# SSFocuser-B-TMC2208.net
KiCad netlist of a schematic drawn in Altium Designer
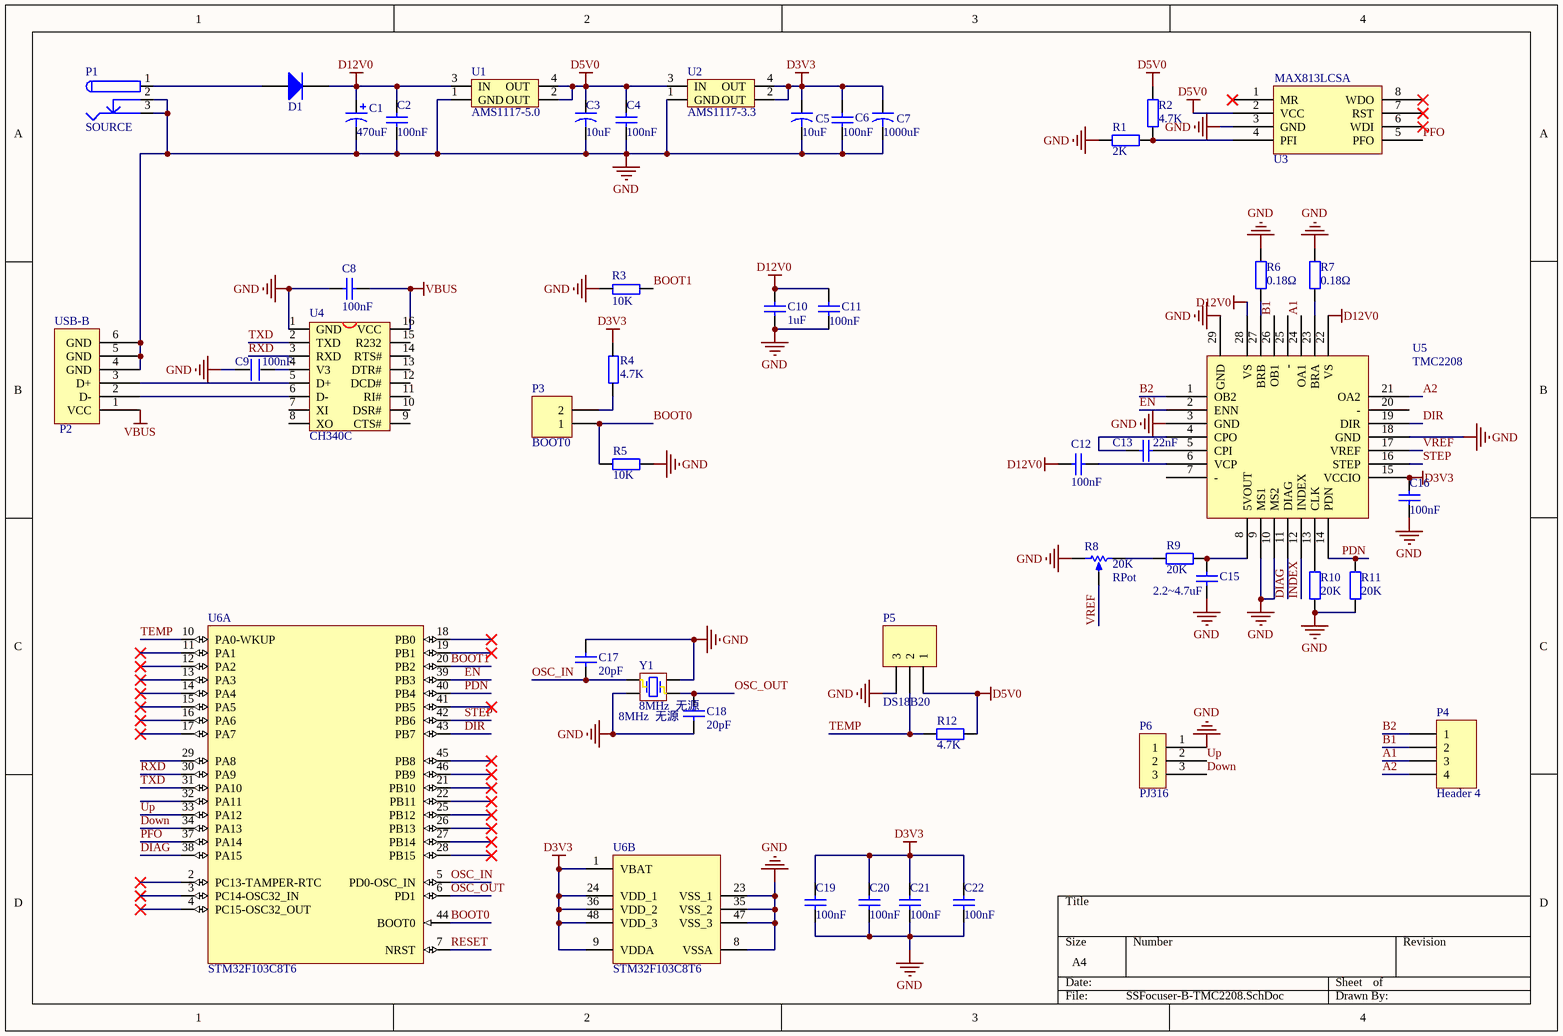
[diagram p0: SSFocuser-B-TMC2208.SchDoc]

(export (version "E")
  (design (tool "Eeschema 10.0.6"))
  (components
    (comp (ref "C1")
      (value "470uF")
      (footprint "16V/470U(CD10X10D5)")
      (description "470UF      16V      CD10X10D5")
      (libsource (lib "平台原理图symbol图库V1.0") (part "C470UF016S"))
    )
    (comp (ref "C2")
      (value "100nF")
      (footprint "0603C")
      (description "Capacitor")
      (fields (field (name "PUBLISHER") "Altium Limited"))
      (libsource (lib "Crazy_PCB") (part "Cap"))
    )
    (comp (ref "C3")
      (value "10uF")
      (footprint "3216")
      (fields (field (name "VAULE") "10uF"))
      (libsource (lib "Crazy_PCB") (part "CAP2"))
    )
    (comp (ref "C4")
      (value "100nF")
      (footprint "0603C")
      (description "Capacitor")
      (fields (field (name "PUBLISHER") "Altium Limited"))
      (libsource (lib "Crazy_PCB") (part "Cap"))
    )
    (comp (ref "C5")
      (value "10uF")
      (footprint "3216")
      (fields (field (name "VAULE") "10uF"))
      (libsource (lib "Crazy_PCB") (part "CAP2"))
    )
    (comp (ref "C6")
      (value "100nF")
      (footprint "0603C")
      (description "Capacitor")
      (fields (field (name "PUBLISHER") "Altium Limited"))
      (libsource (lib "Crazy_PCB") (part "Cap"))
    )
    (comp (ref "C7")
      (value "1000uF")
      (footprint "16V/470U(CD10X10D5)")
      (fields (field (name "VAULE") "1000uF"))
      (libsource (lib "Crazy_PCB") (part "CAP2"))
    )
    (comp (ref "C8")
      (value "100nF")
      (footprint "0603C")
      (description "Capacitor")
      (fields (field (name "PUBLISHER") "Altium Limited"))
      (libsource (lib "Crazy_PCB") (part "Cap"))
    )
    (comp (ref "C9")
      (value "100nF")
      (footprint "0603C")
      (libsource (lib "WarShip V3 STM32103封装库") (part "C"))
    )
    (comp (ref "C10")
      (value "1uF")
      (footprint "1206C")
      (description "Capacitor")
      (fields (field (name "PUBLISHER") "Altium Limited"))
      (libsource (lib "Crazy_PCB") (part "Cap"))
    )
    (comp (ref "C11")
      (value "100nF")
      (footprint "0603C")
      (description "Capacitor")
      (fields (field (name "PUBLISHER") "Altium Limited"))
      (libsource (lib "Crazy_PCB") (part "Cap"))
    )
    (comp (ref "C12")
      (value "100nF")
      (footprint "0603C")
      (description "Capacitor")
      (fields (field (name "PUBLISHER") "Altium Limited"))
      (libsource (lib "Crazy_PCB") (part "Cap"))
    )
    (comp (ref "C13")
      (value "22nF")
      (footprint "0603C")
      (description "Capacitor")
      (fields (field (name "PUBLISHER") "Altium Limited"))
      (libsource (lib "Crazy_PCB") (part "Cap"))
    )
    (comp (ref "C15")
      (value "2.2~4.7uF")
      (footprint "0603C")
      (description "Capacitor")
      (fields (field (name "PUBLISHER") "Altium Limited"))
      (libsource (lib "Crazy_PCB") (part "Cap"))
    )
    (comp (ref "C16")
      (value "100nF")
      (footprint "0603C")
      (description "Capacitor")
      (fields (field (name "PUBLISHER") "Altium Limited"))
      (libsource (lib "Crazy_PCB") (part "Cap"))
    )
    (comp (ref "C17")
      (value "20pF")
      (footprint "0603C")
      (description "Capacitor")
      (fields (field (name "PUBLISHER") "Altium Limited"))
      (libsource (lib "JL_SCH") (part "Cap"))
    )
    (comp (ref "C18")
      (value "20pF")
      (footprint "0603C")
      (description "Capacitor")
      (fields (field (name "PUBLISHER") "Altium Limited"))
      (libsource (lib "JL_SCH") (part "Cap"))
    )
    (comp (ref "C19")
      (value "100nF")
      (footprint "0603C")
      (description "Capacitor")
      (fields (field (name "PUBLISHER") "Altium Limited"))
      (libsource (lib "Crazy_PCB") (part "Cap"))
    )
    (comp (ref "C20")
      (value "100nF")
      (footprint "0603C")
      (description "Capacitor")
      (fields (field (name "PUBLISHER") "Altium Limited"))
      (libsource (lib "Crazy_PCB") (part "Cap"))
    )
    (comp (ref "C21")
      (value "100nF")
      (footprint "0603C")
      (description "Capacitor")
      (fields (field (name "PUBLISHER") "Altium Limited"))
      (libsource (lib "Crazy_PCB") (part "Cap"))
    )
    (comp (ref "C22")
      (value "100nF")
      (footprint "0603C")
      (description "Capacitor")
      (fields (field (name "PUBLISHER") "Altium Limited"))
      (libsource (lib "Crazy_PCB") (part "Cap"))
    )
    (comp (ref "D1")
      (value "M7")
      (footprint "DO-214AC")
      (description "High Conductance Fast Diode")
      (fields (field (name "PUBLISHER") "Altium Limited"))
      (libsource (lib "Crazy_PCB") (part "Diode"))
    )
    (comp (ref "P1")
      (value "SOURCE")
      (footprint "DC_5.5MM")
      (fields (field (name "PUBLISHER") "Altium Limited"))
      (libsource (lib "Crazy_PCB") (part "SOURCE"))
    )
    (comp (ref "P2") (value "USB-B") (footprint "USB-B") (libsource (lib "DX") (part "USB-B")))
    (comp (ref "P3")
      (value "BOOT0")
      (footprint "HDR1X2")
      (description "Header, 2-Pin")
      (fields (field (name "PUBLISHER") "Altium Limited"))
      (libsource (lib "Miscellaneous Connectors") (part "MHDR1X2"))
    )
    (comp (ref "P4")
      (value "Header 4")
      (footprint "XH_4_V")
      (description "Header, 4-Pin")
      (fields (field (name "PUBLISHER") "Altium Limited"))
      (libsource (lib "Miscellaneous Connectors") (part "Header 4"))
    )
    (comp (ref "P5")
      (value "DS18B20")
      (footprint "TO-92B")
      (description "Header, 3-Pin")
      (fields (field (name "PUBLISHER") "Altium Limited"))
      (libsource (lib "Miscellaneous Connectors") (part "Header 3"))
    )
    (comp (ref "P6") (value "PJ316") (footprint "PJ316") (libsource (lib "SS") (part "PJ316")))
    (comp (ref "R1")
      (value "2K")
      (footprint "0603R")
      (description "Resistor")
      (fields (field (name "PUBLISHER") "Altium Limited"))
      (libsource (lib "") (part "RES_3"))
    )
    (comp (ref "R2")
      (value "4.7K")
      (footprint "0603R")
      (description "Resistor")
      (fields (field (name "PUBLISHER") "Altium Limited"))
      (libsource (lib "") (part "RES_1"))
    )
    (comp (ref "R3") (value "10K") (footprint "0603R") (libsource (lib "WarShip V3 STM32103封装库") (part "R")))
    (comp (ref "R4") (value "4.7K") (footprint "0603R") (libsource (lib "WarShip V3 STM32103封装库") (part "R")))
    (comp (ref "R5")
      (value "10K")
      (footprint "0603R")
      (description "Resistor")
      (fields (field (name "PUBLISHER") "Altium Limited"))
      (libsource (lib "") (part "RES_2"))
    )
    (comp (ref "R6")
      (value "0.18Ω")
      (footprint "1206R")
      (description "Resistor")
      (fields (field (name "PUBLISHER") "Altium Limited"))
      (libsource (lib "Crazy_PCB") (part "RES"))
    )
    (comp (ref "R7")
      (value "0.18Ω")
      (footprint "1206R")
      (description "Resistor")
      (fields (field (name "PUBLISHER") "Altium Limited"))
      (libsource (lib "Crazy_PCB") (part "RES"))
    )
    (comp (ref "R8")
      (value "RPot")
      (footprint "VR_SMD")
      (description "Potentiometer")
      (fields (field (name "ALTIUM_VALUE") "20K") (field (name "PUBLISHER") "Altium Limited"))
      (libsource (lib "Miscellaneous Devices") (part "RPot"))
    )
    (comp (ref "R9")
      (value "20K")
      (footprint "0603R")
      (description "Resistor")
      (fields (field (name "PUBLISHER") "Altium Limited"))
      (libsource (lib "") (part "RES_3"))
    )
    (comp (ref "R10")
      (value "20K")
      (footprint "0603R")
      (description "Resistor")
      (fields (field (name "PUBLISHER") "Altium Limited"))
      (libsource (lib "") (part "RES_1"))
    )
    (comp (ref "R11")
      (value "20K")
      (footprint "0603R")
      (description "Resistor")
      (fields (field (name "PUBLISHER") "Altium Limited"))
      (libsource (lib "") (part "RES_1"))
    )
    (comp (ref "R12")
      (value "4.7K")
      (footprint "0603R")
      (description "Resistor")
      (fields (field (name "PUBLISHER") "Altium Limited"))
      (libsource (lib "") (part "RES_2"))
    )
    (comp (ref "U1")
      (value "AMS1117-5.0")
      (footprint "SOT223")
      (libsource (lib "MiniSTM32 V3.0封装库") (part "AMS1117"))
    )
    (comp (ref "U2")
      (value "AMS1117-3.3")
      (footprint "SOT223")
      (libsource (lib "MiniSTM32 V3.0封装库") (part "AMS1117"))
    )
    (comp (ref "U3") (value "MAX813LCSA") (footprint "SOP-8") (libsource (lib "DX") (part "MAX813L")))
    (comp (ref "U4")
      (value "CH340C")
      (footprint "SO-16")
      (description "USB2UART")
      (libsource (lib "WarShip V3 STM32103封装库") (part "CH340G"))
    )
    (comp (ref "U5") (value "TMC2208") (footprint "QFN28") (libsource (lib "SS") (part "TMC2208")))
    (comp (ref "U6")
      (value "STM32F103C8T6")
      (footprint "LQFP48_N")
      (libsource (lib "STMicroelectronics STM32 F1") (part "STM32F103C8T6"))
    )
    (comp (ref "Y1")
      (value "8MHz  无源")
      (footprint "X3225")
      (description "Crystal Oscillator")
      (fields (field (name "ALTIUM_VALUE") "8MHz  无源") (field (name "PUBLISHER") "Altium Limited"))
      (libsource (lib "JL_SCH") (part "XTAL_1"))
    )
  )
  (nets
    (net (code "1") (name "/A1") (class "Default")
      (node (ref "P4") (pin "3") (pinfunction "3_3") (pintype "passive"))
      (node (ref "U5") (pin "24") (pinfunction "OA1_24") (pintype "passive"))
    )
    (net (code "2") (name "/A2") (class "Default")
      (node (ref "P4") (pin "4") (pinfunction "4_4") (pintype "passive"))
      (node (ref "U5") (pin "21") (pinfunction "OA2_21") (pintype "passive"))
    )
    (net (code "3") (name "/B1") (class "Default")
      (node (ref "P4") (pin "2") (pinfunction "2_2") (pintype "passive"))
      (node (ref "U5") (pin "26") (pinfunction "OB1_26") (pintype "passive"))
    )
    (net (code "4") (name "/B2") (class "Default")
      (node (ref "P4") (pin "1") (pinfunction "1_1") (pintype "passive"))
      (node (ref "U5") (pin "1") (pinfunction "OB2_1") (pintype "passive"))
    )
    (net (code "5") (name "/BOOT0") (class "Default")
      (node (ref "P3") (pin "1") (pinfunction "1_1") (pintype "passive"))
      (node (ref "R5") (pin "1") (pinfunction "1_1") (pintype "passive"))
      (node (ref "U6") (pin "44") (pinfunction "BOOT0_44") (pintype "input"))
    )
    (net (code "6") (name "/BOOT1") (class "Default")
      (node (ref "R3") (pin "2") (pintype "passive"))
      (node (ref "U6") (pin "20") (pinfunction "PB2_20") (pintype "bidirectional"))
    )
    (net (code "7") (name "/DIAG") (class "Default")
      (node (ref "U5") (pin "11") (pinfunction "DIAG_11") (pintype "passive"))
      (node (ref "U6") (pin "38") (pinfunction "PA15_38") (pintype "bidirectional"))
    )
    (net (code "8") (name "/DIR") (class "Default")
      (node (ref "U5") (pin "19") (pinfunction "DIR_19") (pintype "passive"))
      (node (ref "U6") (pin "43") (pinfunction "PB7_43") (pintype "bidirectional"))
    )
    (net (code "9") (name "/Down") (class "Default")
      (node (ref "P6") (pin "3") (pinfunction "3_3") (pintype "passive"))
      (node (ref "U6") (pin "34") (pinfunction "PA13_34") (pintype "bidirectional"))
    )
    (net (code "10") (name "/EN") (class "Default")
      (node (ref "U5") (pin "2") (pinfunction "ENN_2") (pintype "passive"))
      (node (ref "U6") (pin "39") (pinfunction "PB3_39") (pintype "bidirectional"))
    )
    (net (code "11") (name "/INDEX") (class "Default")
      (node (ref "U5") (pin "12") (pinfunction "INDEX_12") (pintype "passive"))
    )
    (net (code "12") (name "/OSC_IN") (class "Default")
      (node (ref "C17") (pin "1") (pinfunction "1_1") (pintype "passive"))
      (node (ref "U6") (pin "5") (pinfunction "PD0-OSC_IN_5") (pintype "bidirectional"))
      (node (ref "Y1") (pin "1") (pinfunction "OSC1_1") (pintype "passive"))
    )
    (net (code "13") (name "/OSC_OUT") (class "Default")
      (node (ref "C18") (pin "1") (pinfunction "1_1") (pintype "passive"))
      (node (ref "U6") (pin "6") (pinfunction "PD1_6") (pintype "bidirectional"))
      (node (ref "Y1") (pin "3") (pinfunction "OSC2_3") (pintype "passive"))
    )
    (net (code "14") (name "/PDN") (class "Default")
      (node (ref "R11") (pin "2") (pinfunction "2_2") (pintype "passive"))
      (node (ref "U5") (pin "14") (pinfunction "PDN_14") (pintype "passive"))
      (node (ref "U6") (pin "40") (pinfunction "PB4_40") (pintype "bidirectional"))
    )
    (net (code "15") (name "/PFO") (class "Default")
      (node (ref "U3") (pin "5") (pinfunction "PFO_5") (pintype "passive"))
      (node (ref "U6") (pin "37") (pinfunction "PA14_37") (pintype "bidirectional"))
    )
    (net (code "16") (name "/RESET") (class "Default")
      (node (ref "U6") (pin "7") (pinfunction "NRST_7") (pintype "bidirectional"))
    )
    (net (code "17") (name "/RXD") (class "Default")
      (node (ref "U4") (pin "3") (pinfunction "RXD_3") (pintype "passive"))
      (node (ref "U6") (pin "30") (pinfunction "PA9_30") (pintype "bidirectional"))
    )
    (net (code "18") (name "/STEP") (class "Default")
      (node (ref "U5") (pin "16") (pinfunction "STEP_16") (pintype "passive"))
      (node (ref "U6") (pin "42") (pinfunction "PB6_42") (pintype "bidirectional"))
    )
    (net (code "19") (name "/TEMP") (class "Default")
      (node (ref "P5") (pin "2") (pinfunction "2_2") (pintype "passive"))
      (node (ref "R12") (pin "1") (pinfunction "1_1") (pintype "passive"))
      (node (ref "U6") (pin "10") (pinfunction "PA0-WKUP_10") (pintype "bidirectional"))
    )
    (net (code "20") (name "/TXD") (class "Default")
      (node (ref "U4") (pin "2") (pinfunction "TXD_2") (pintype "passive"))
      (node (ref "U6") (pin "31") (pinfunction "PA10_31") (pintype "bidirectional"))
    )
    (net (code "21") (name "/Up") (class "Default")
      (node (ref "P6") (pin "2") (pinfunction "2_2") (pintype "passive"))
      (node (ref "U6") (pin "33") (pinfunction "PA12_33") (pintype "bidirectional"))
    )
    (net (code "22") (name "/VREF") (class "Default")
      (node (ref "R8") (pin "3") (pinfunction "TAP_3") (pintype "passive"))
      (node (ref "U5") (pin "17") (pinfunction "VREF_17") (pintype "passive"))
    )
    (net (code "23") (name "D3V3") (class "Default")
      (node (ref "C16") (pin "2") (pinfunction "2_2") (pintype "passive"))
      (node (ref "C19") (pin "2") (pinfunction "2_2") (pintype "passive"))
      (node (ref "C20") (pin "2") (pinfunction "2_2") (pintype "passive"))
      (node (ref "C21") (pin "2") (pinfunction "2_2") (pintype "passive"))
      (node (ref "C22") (pin "2") (pinfunction "2_2") (pintype "passive"))
      (node (ref "C5") (pin "1") (pinfunction "1_1") (pintype "passive"))
      (node (ref "C6") (pin "2") (pinfunction "2_2") (pintype "passive"))
      (node (ref "C7") (pin "1") (pinfunction "1_1") (pintype "passive"))
      (node (ref "R4") (pin "2") (pintype "passive"))
      (node (ref "U2") (pin "2") (pinfunction "OUT_2") (pintype "passive"))
      (node (ref "U2") (pin "4") (pinfunction "OUT_4") (pintype "passive"))
      (node (ref "U5") (pin "15") (pinfunction "VCCIO_15") (pintype "passive"))
      (node (ref "U6") (pin "1") (pinfunction "VBAT_1") (pintype "power_in"))
      (node (ref "U6") (pin "24") (pinfunction "VDD_1_24") (pintype "power_in"))
      (node (ref "U6") (pin "36") (pinfunction "VDD_2_36") (pintype "power_in"))
      (node (ref "U6") (pin "48") (pinfunction "VDD_3_48") (pintype "power_in"))
      (node (ref "U6") (pin "9") (pinfunction "VDDA_9") (pintype "power_in"))
    )
    (net (code "24") (name "D5V0") (class "Default")
      (node (ref "C3") (pin "1") (pinfunction "1_1") (pintype "passive"))
      (node (ref "C4") (pin "2") (pinfunction "2_2") (pintype "passive"))
      (node (ref "P5") (pin "1") (pinfunction "1_1") (pintype "passive"))
      (node (ref "R12") (pin "2") (pinfunction "2_2") (pintype "passive"))
      (node (ref "R2") (pin "2") (pinfunction "2_2") (pintype "passive"))
      (node (ref "U1") (pin "2") (pinfunction "OUT_2") (pintype "passive"))
      (node (ref "U1") (pin "4") (pinfunction "OUT_4") (pintype "passive"))
      (node (ref "U2") (pin "3") (pinfunction "IN_3") (pintype "passive"))
      (node (ref "U3") (pin "2") (pinfunction "VCC_2") (pintype "passive"))
    )
    (net (code "25") (name "D12V0") (class "Default")
      (node (ref "C1") (pin "1") (pinfunction "1_1") (pintype "passive"))
      (node (ref "C10") (pin "1") (pinfunction "1_1") (pintype "passive"))
      (node (ref "C11") (pin "2") (pinfunction "2_2") (pintype "passive"))
      (node (ref "C12") (pin "2") (pinfunction "2_2") (pintype "passive"))
      (node (ref "C2") (pin "2") (pinfunction "2_2") (pintype "passive"))
      (node (ref "D1") (pin "2") (pinfunction "K_2") (pintype "passive"))
      (node (ref "U1") (pin "3") (pinfunction "IN_3") (pintype "passive"))
      (node (ref "U5") (pin "22") (pinfunction "VS_22") (pintype "passive"))
      (node (ref "U5") (pin "28") (pinfunction "VS_28") (pintype "passive"))
    )
    (net (code "26") (name "GND") (class "Default")
      (node (ref "C1") (pin "2") (pinfunction "2_2") (pintype "passive"))
      (node (ref "C10") (pin "2") (pinfunction "2_2") (pintype "passive"))
      (node (ref "C11") (pin "1") (pinfunction "1_1") (pintype "passive"))
      (node (ref "C15") (pin "1") (pinfunction "1_1") (pintype "passive"))
      (node (ref "C16") (pin "1") (pinfunction "1_1") (pintype "passive"))
      (node (ref "C17") (pin "2") (pinfunction "2_2") (pintype "passive"))
      (node (ref "C18") (pin "2") (pinfunction "2_2") (pintype "passive"))
      (node (ref "C19") (pin "1") (pinfunction "1_1") (pintype "passive"))
      (node (ref "C2") (pin "1") (pinfunction "1_1") (pintype "passive"))
      (node (ref "C20") (pin "1") (pinfunction "1_1") (pintype "passive"))
      (node (ref "C21") (pin "1") (pinfunction "1_1") (pintype "passive"))
      (node (ref "C22") (pin "1") (pinfunction "1_1") (pintype "passive"))
      (node (ref "C3") (pin "2") (pinfunction "2_2") (pintype "passive"))
      (node (ref "C4") (pin "1") (pinfunction "1_1") (pintype "passive"))
      (node (ref "C5") (pin "2") (pinfunction "2_2") (pintype "passive"))
      (node (ref "C6") (pin "1") (pinfunction "1_1") (pintype "passive"))
      (node (ref "C7") (pin "2") (pinfunction "2_2") (pintype "passive"))
      (node (ref "C8") (pin "1") (pinfunction "1_1") (pintype "passive"))
      (node (ref "C9") (pin "1") (pintype "passive"))
      (node (ref "P1") (pin "2") (pinfunction "2_2") (pintype "power_in"))
      (node (ref "P1") (pin "3") (pinfunction "3_3") (pintype "power_in"))
      (node (ref "P2") (pin "4") (pinfunction "GND_4") (pintype "passive"))
      (node (ref "P2") (pin "5") (pinfunction "GND_5") (pintype "passive"))
      (node (ref "P2") (pin "6") (pinfunction "GND_6") (pintype "passive"))
      (node (ref "P5") (pin "3") (pinfunction "3_3") (pintype "passive"))
      (node (ref "P6") (pin "1") (pinfunction "1_1") (pintype "passive"))
      (node (ref "R1") (pin "2") (pinfunction "2_2") (pintype "passive"))
      (node (ref "R10") (pin "1") (pinfunction "1_1") (pintype "passive"))
      (node (ref "R11") (pin "1") (pinfunction "1_1") (pintype "passive"))
      (node (ref "R3") (pin "1") (pintype "passive"))
      (node (ref "R5") (pin "2") (pinfunction "2_2") (pintype "passive"))
      (node (ref "R6") (pin "1") (pinfunction "1_1") (pintype "passive"))
      (node (ref "R7") (pin "1") (pinfunction "1_1") (pintype "passive"))
      (node (ref "R8") (pin "1") (pinfunction "TOP_1") (pintype "passive"))
      (node (ref "U1") (pin "1") (pinfunction "GND_1") (pintype "passive"))
      (node (ref "U2") (pin "1") (pinfunction "GND_1") (pintype "passive"))
      (node (ref "U3") (pin "3") (pinfunction "GND_3") (pintype "passive"))
      (node (ref "U4") (pin "1") (pinfunction "GND_1") (pintype "passive"))
      (node (ref "U5") (pin "10") (pinfunction "MS2_10") (pintype "passive"))
      (node (ref "U5") (pin "18") (pinfunction "GND_18") (pintype "passive"))
      (node (ref "U5") (pin "29") (pinfunction "GND_29") (pintype "passive"))
      (node (ref "U5") (pin "3") (pinfunction "GND_3") (pintype "passive"))
      (node (ref "U5") (pin "9") (pinfunction "MS1_9") (pintype "passive"))
      (node (ref "U6") (pin "23") (pinfunction "VSS_1_23") (pintype "power_in"))
      (node (ref "U6") (pin "35") (pinfunction "VSS_2_35") (pintype "power_in"))
      (node (ref "U6") (pin "47") (pinfunction "VSS_3_47") (pintype "power_in"))
      (node (ref "U6") (pin "8") (pinfunction "VSSA_8") (pintype "power_in"))
      (node (ref "Y1") (pin "2") (pinfunction "NA_2") (pintype "passive"))
      (node (ref "Y1") (pin "4") (pinfunction "NA_4") (pintype "passive"))
    )
    (net (code "27") (name "Net-(D1-A)") (class "Default")
      (node (ref "D1") (pin "1") (pinfunction "A_1") (pintype "passive"))
      (node (ref "P1") (pin "1") (pinfunction "1_1") (pintype "power_in"))
    )
    (net (code "28") (name "Net-(P2-D+)") (class "Default")
      (node (ref "P2") (pin "3") (pinfunction "D+_3") (pintype "passive"))
      (node (ref "U4") (pin "5") (pinfunction "D+_5") (pintype "passive"))
    )
    (net (code "29") (name "Net-(P2-D-)") (class "Default")
      (node (ref "P2") (pin "2") (pinfunction "D-_2") (pintype "passive"))
      (node (ref "U4") (pin "6") (pinfunction "D-_6") (pintype "passive"))
    )
    (net (code "30") (name "Net-(P3-Pad2)") (class "Default")
      (node (ref "P3") (pin "2") (pinfunction "2_2") (pintype "passive"))
      (node (ref "R4") (pin "1") (pintype "passive"))
    )
    (net (code "31") (name "Net-(R8-BOT)") (class "Default")
      (node (ref "R8") (pin "2") (pinfunction "BOT_2") (pintype "passive"))
      (node (ref "R9") (pin "2") (pinfunction "2_2") (pintype "passive"))
    )
    (net (code "32") (name "Net-(U3-PFI)") (class "Default")
      (node (ref "R1") (pin "1") (pinfunction "1_1") (pintype "passive"))
      (node (ref "R2") (pin "1") (pinfunction "1_1") (pintype "passive"))
      (node (ref "U3") (pin "4") (pinfunction "PFI_4") (pintype "passive"))
    )
    (net (code "33") (name "Net-(U4-V3)") (class "Default")
      (node (ref "C9") (pin "2") (pintype "passive"))
      (node (ref "U4") (pin "4") (pinfunction "V3_4") (pintype "passive"))
    )
    (net (code "34") (name "Net-(U5-5VOUT)") (class "Default")
      (node (ref "C15") (pin "2") (pinfunction "2_2") (pintype "passive"))
      (node (ref "R9") (pin "1") (pinfunction "1_1") (pintype "passive"))
      (node (ref "U5") (pin "8") (pinfunction "5VOUT_8") (pintype "passive"))
    )
    (net (code "35") (name "Net-(U5-BRA)") (class "Default")
      (node (ref "R7") (pin "2") (pinfunction "2_2") (pintype "passive"))
      (node (ref "U5") (pin "23") (pinfunction "BRA_23") (pintype "passive"))
    )
    (net (code "36") (name "Net-(U5-BRB)") (class "Default")
      (node (ref "R6") (pin "2") (pinfunction "2_2") (pintype "passive"))
      (node (ref "U5") (pin "27") (pinfunction "BRB_27") (pintype "passive"))
    )
    (net (code "37") (name "Net-(U5-CLK)") (class "Default")
      (node (ref "R10") (pin "2") (pinfunction "2_2") (pintype "passive"))
      (node (ref "U5") (pin "13") (pinfunction "CLK_13") (pintype "passive"))
    )
    (net (code "38") (name "Net-(U5-CPI)") (class "Default")
      (node (ref "C13") (pin "1") (pinfunction "1_1") (pintype "passive"))
      (node (ref "U5") (pin "5") (pinfunction "CPI_5") (pintype "passive"))
    )
    (net (code "39") (name "Net-(U5-CPO)") (class "Default")
      (node (ref "C13") (pin "2") (pinfunction "2_2") (pintype "passive"))
      (node (ref "U5") (pin "4") (pinfunction "CPO_4") (pintype "passive"))
    )
    (net (code "40") (name "Net-(U5-VCP)") (class "Default")
      (node (ref "C12") (pin "1") (pinfunction "1_1") (pintype "passive"))
      (node (ref "U5") (pin "6") (pinfunction "VCP_6") (pintype "passive"))
    )
    (net (code "41") (name "VBUS") (class "Default")
      (node (ref "C8") (pin "2") (pinfunction "2_2") (pintype "passive"))
      (node (ref "P2") (pin "1") (pinfunction "VCC_1") (pintype "passive"))
      (node (ref "U4") (pin "16") (pinfunction "VCC_16") (pintype "passive"))
    )
    (net (code "42") (name "unconnected-(U3-MR-Pad1)") (class "Default")
      (node (ref "U3") (pin "1") (pinfunction "MR_1") (pintype "passive+no_connect"))
    )
    (net (code "43") (name "unconnected-(U3-RST-Pad7)") (class "Default")
      (node (ref "U3") (pin "7") (pinfunction "RST_7") (pintype "passive+no_connect"))
    )
    (net (code "44") (name "unconnected-(U3-WDI-Pad6)") (class "Default")
      (node (ref "U3") (pin "6") (pinfunction "WDI_6") (pintype "passive+no_connect"))
    )
    (net (code "45") (name "unconnected-(U3-WDO-Pad8)") (class "Default")
      (node (ref "U3") (pin "8") (pinfunction "WDO_8") (pintype "passive+no_connect"))
    )
    (net (code "46") (name "unconnected-(U4-CTS#-Pad9)") (class "Default")
      (node (ref "U4") (pin "9") (pinfunction "CTS#_9") (pintype "passive"))
    )
    (net (code "47") (name "unconnected-(U4-DCD#-Pad12)") (class "Default")
      (node (ref "U4") (pin "12") (pinfunction "DCD#_12") (pintype "passive"))
    )
    (net (code "48") (name "unconnected-(U4-DSR#-Pad10)") (class "Default")
      (node (ref "U4") (pin "10") (pinfunction "DSR#_10") (pintype "passive"))
    )
    (net (code "49") (name "unconnected-(U4-DTR#-Pad13)") (class "Default")
      (node (ref "U4") (pin "13") (pinfunction "DTR#_13") (pintype "passive"))
    )
    (net (code "50") (name "unconnected-(U4-R232-Pad15)") (class "Default")
      (node (ref "U4") (pin "15") (pinfunction "R232_15") (pintype "passive"))
    )
    (net (code "51") (name "unconnected-(U4-RI#-Pad11)") (class "Default")
      (node (ref "U4") (pin "11") (pinfunction "RI#_11") (pintype "passive"))
    )
    (net (code "52") (name "unconnected-(U4-RTS#-Pad14)") (class "Default")
      (node (ref "U4") (pin "14") (pinfunction "RTS#_14") (pintype "passive"))
    )
    (net (code "53") (name "unconnected-(U4-XI-Pad7)") (class "Default")
      (node (ref "U4") (pin "7") (pinfunction "XI_7") (pintype "passive"))
    )
    (net (code "54") (name "unconnected-(U4-XO-Pad8)") (class "Default")
      (node (ref "U4") (pin "8") (pinfunction "XO_8") (pintype "passive"))
    )
    (net (code "55") (name "unconnected-(U5---Pad7)") (class "Default")
      (node (ref "U5") (pin "7") (pinfunction "-_7") (pintype "passive"))
    )
    (net (code "56") (name "unconnected-(U5---Pad20)") (class "Default")
      (node (ref "U5") (pin "20") (pinfunction "-_20") (pintype "passive"))
    )
    (net (code "57") (name "unconnected-(U5---Pad25)") (class "Default")
      (node (ref "U5") (pin "25") (pinfunction "-_25") (pintype "passive"))
    )
    (net (code "58") (name "unconnected-(U6A-PA1-Pad11)") (class "Default")
      (node (ref "U6") (pin "11") (pinfunction "PA1_11") (pintype "bidirectional+no_connect"))
    )
    (net (code "59") (name "unconnected-(U6A-PA2-Pad12)") (class "Default")
      (node (ref "U6") (pin "12") (pinfunction "PA2_12") (pintype "bidirectional+no_connect"))
    )
    (net (code "60") (name "unconnected-(U6A-PA3-Pad13)") (class "Default")
      (node (ref "U6") (pin "13") (pinfunction "PA3_13") (pintype "bidirectional+no_connect"))
    )
    (net (code "61") (name "unconnected-(U6A-PA4-Pad14)") (class "Default")
      (node (ref "U6") (pin "14") (pinfunction "PA4_14") (pintype "bidirectional+no_connect"))
    )
    (net (code "62") (name "unconnected-(U6A-PA5-Pad15)") (class "Default")
      (node (ref "U6") (pin "15") (pinfunction "PA5_15") (pintype "bidirectional+no_connect"))
    )
    (net (code "63") (name "unconnected-(U6A-PA6-Pad16)") (class "Default")
      (node (ref "U6") (pin "16") (pinfunction "PA6_16") (pintype "bidirectional+no_connect"))
    )
    (net (code "64") (name "unconnected-(U6A-PA7-Pad17)") (class "Default")
      (node (ref "U6") (pin "17") (pinfunction "PA7_17") (pintype "bidirectional+no_connect"))
    )
    (net (code "65") (name "unconnected-(U6A-PA8-Pad29)") (class "Default")
      (node (ref "U6") (pin "29") (pinfunction "PA8_29") (pintype "bidirectional"))
    )
    (net (code "66") (name "unconnected-(U6A-PA11-Pad32)") (class "Default")
      (node (ref "U6") (pin "32") (pinfunction "PA11_32") (pintype "bidirectional"))
    )
    (net (code "67") (name "unconnected-(U6A-PB0-Pad18)") (class "Default")
      (node (ref "U6") (pin "18") (pinfunction "PB0_18") (pintype "bidirectional+no_connect"))
    )
    (net (code "68") (name "unconnected-(U6A-PB1-Pad19)") (class "Default")
      (node (ref "U6") (pin "19") (pinfunction "PB1_19") (pintype "bidirectional+no_connect"))
    )
    (net (code "69") (name "unconnected-(U6A-PB5-Pad41)") (class "Default")
      (node (ref "U6") (pin "41") (pinfunction "PB5_41") (pintype "bidirectional+no_connect"))
    )
    (net (code "70") (name "unconnected-(U6A-PB8-Pad45)") (class "Default")
      (node (ref "U6") (pin "45") (pinfunction "PB8_45") (pintype "bidirectional+no_connect"))
    )
    (net (code "71") (name "unconnected-(U6A-PB9-Pad46)") (class "Default")
      (node (ref "U6") (pin "46") (pinfunction "PB9_46") (pintype "bidirectional+no_connect"))
    )
    (net (code "72") (name "unconnected-(U6A-PB10-Pad21)") (class "Default")
      (node (ref "U6") (pin "21") (pinfunction "PB10_21") (pintype "bidirectional+no_connect"))
    )
    (net (code "73") (name "unconnected-(U6A-PB11-Pad22)") (class "Default")
      (node (ref "U6") (pin "22") (pinfunction "PB11_22") (pintype "bidirectional+no_connect"))
    )
    (net (code "74") (name "unconnected-(U6A-PB12-Pad25)") (class "Default")
      (node (ref "U6") (pin "25") (pinfunction "PB12_25") (pintype "bidirectional+no_connect"))
    )
    (net (code "75") (name "unconnected-(U6A-PB13-Pad26)") (class "Default")
      (node (ref "U6") (pin "26") (pinfunction "PB13_26") (pintype "bidirectional+no_connect"))
    )
    (net (code "76") (name "unconnected-(U6A-PB14-Pad27)") (class "Default")
      (node (ref "U6") (pin "27") (pinfunction "PB14_27") (pintype "bidirectional+no_connect"))
    )
    (net (code "77") (name "unconnected-(U6A-PB15-Pad28)") (class "Default")
      (node (ref "U6") (pin "28") (pinfunction "PB15_28") (pintype "bidirectional+no_connect"))
    )
    (net (code "78") (name "unconnected-(U6A-PC13-TAMPER-RTC-Pad2)") (class "Default")
      (node (ref "U6") (pin "2") (pinfunction "PC13-TAMPER-RTC_2") (pintype "bidirectional+no_connect"))
    )
    (net (code "79") (name "unconnected-(U6A-PC14-OSC32_IN-Pad3)") (class "Default")
      (node (ref "U6") (pin "3") (pinfunction "PC14-OSC32_IN_3") (pintype "bidirectional+no_connect"))
    )
    (net (code "80") (name "unconnected-(U6A-PC15-OSC32_OUT-Pad4)") (class "Default")
      (node (ref "U6") (pin "4") (pinfunction "PC15-OSC32_OUT_4") (pintype "bidirectional+no_connect"))
    )
  )
)
